# ArduOSD_Simple2222.net
KiCad netlist of a schematic drawn in EAGLE
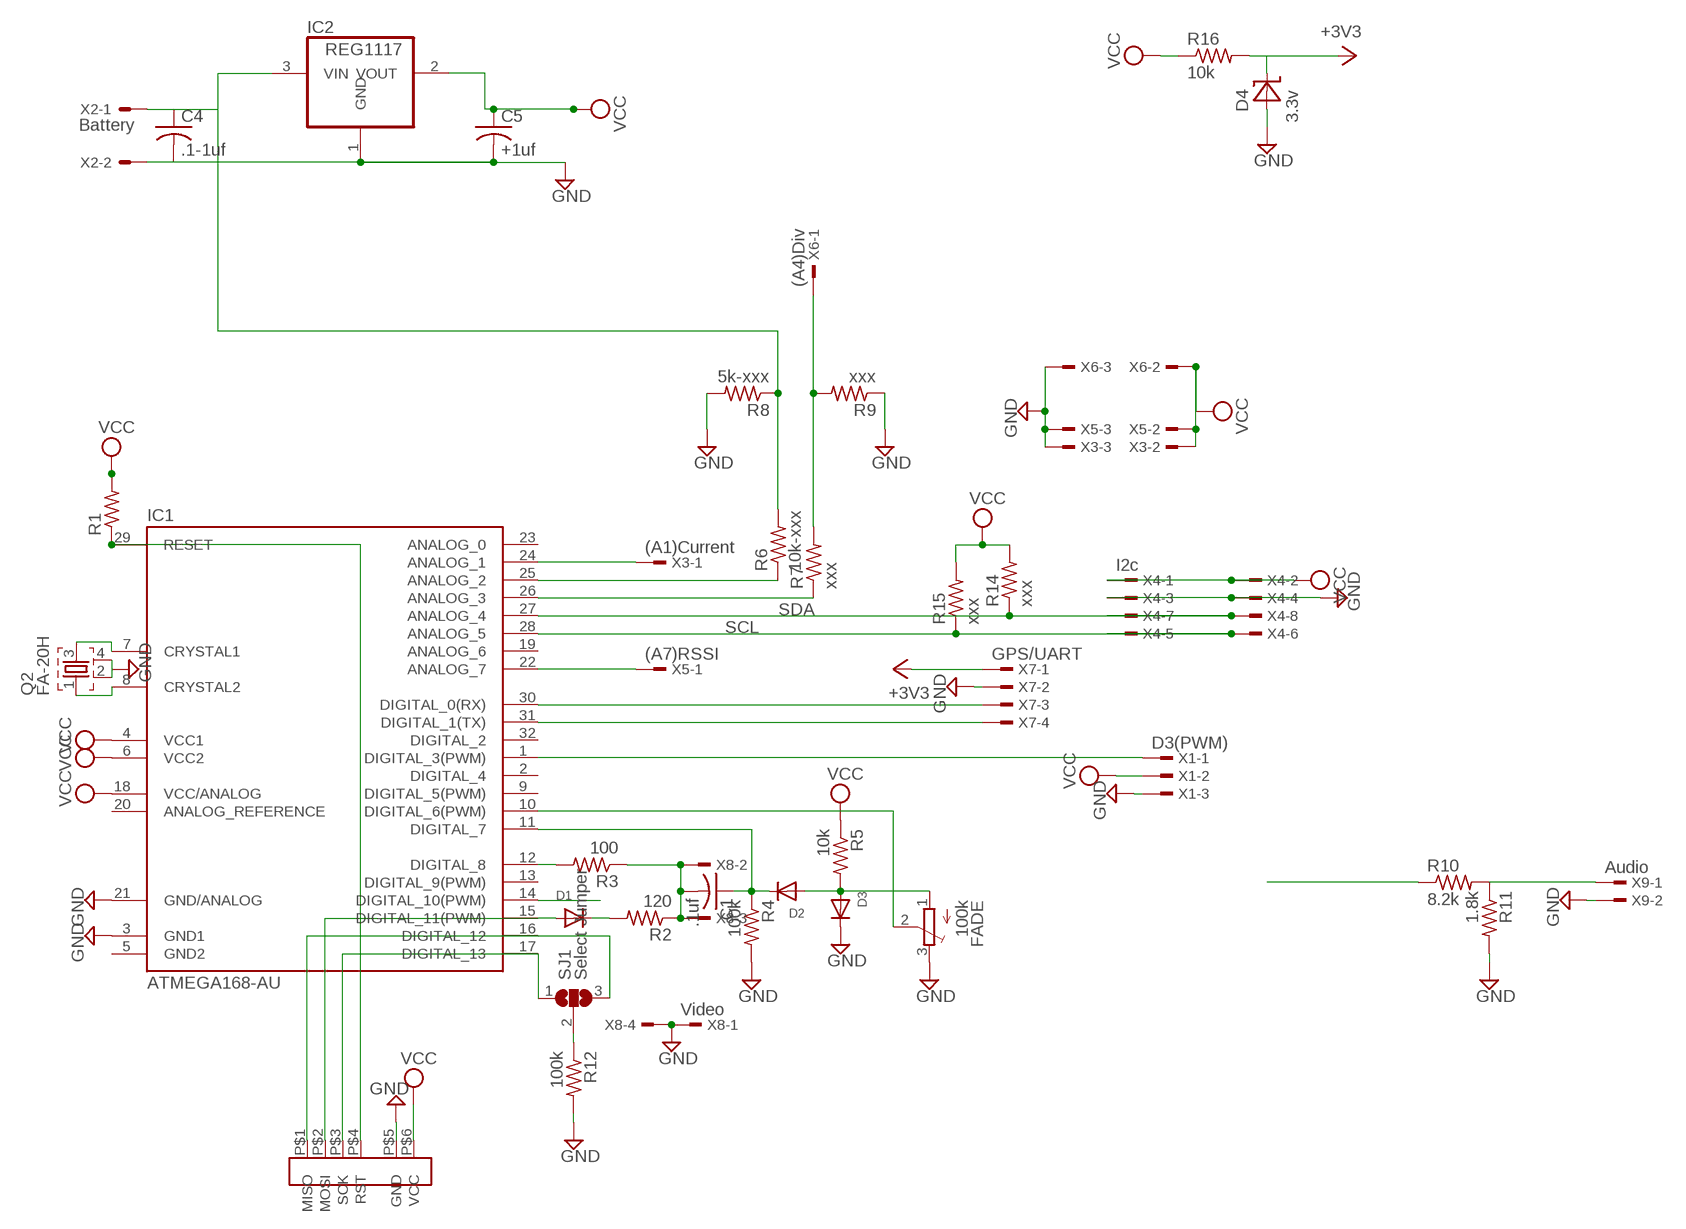
[diagram p0: schematic, sheet 1]

(export (version "E")
  (design (tool "Eeschema 10.0.6"))
  (components
    (comp (ref "C1")
      (value ".1uf")
      (footprint "eagle-import:C0805K")
      (libsource (lib "eagle-import") (part "C-USC0805K"))
    )
    (comp (ref "C4")
      (value ".1-1uf")
      (footprint "eagle-import:C0805K")
      (libsource (lib "eagle-import") (part "C-USC0805K"))
    )
    (comp (ref "C5")
      (value "+1uf")
      (footprint "eagle-import:C0805K")
      (libsource (lib "eagle-import") (part "C-USC0805K"))
    )
    (comp (ref "D1")
      (value "DIODESOT23_WAVE")
      (footprint "eagle-import:SOT23-W")
      (libsource (lib "eagle-import") (part "DIODESOT23_WAVE"))
    )
    (comp (ref "D2")
      (value "DIODESOT23_WAVE")
      (footprint "eagle-import:SOT23-W")
      (libsource (lib "eagle-import") (part "DIODESOT23_WAVE"))
    )
    (comp (ref "D3")
      (value "DIODESOT23_WAVE")
      (footprint "eagle-import:SOT23-W")
      (libsource (lib "eagle-import") (part "DIODESOT23_WAVE"))
    )
    (comp (ref "D4")
      (value "3.3v")
      (footprint "eagle-import:SOD-123")
      (libsource (lib "eagle-import") (part "ZENER_SOD123"))
    )
    (comp (ref "FADE")
      (value "100k")
      (footprint "eagle-import:TC33X")
      (libsource (lib "eagle-import") (part "TRIMPOTTC33X"))
    )
    (comp (ref "IC1")
      (value "ATMEGA168-AU")
      (footprint "eagle-import:TQFP32-08")
      (libsource (lib "eagle-import") (part "ATMEGA168-AU"))
    )
    (comp (ref "IC2")
      (value "REG1117")
      (footprint "eagle-import:SOT223")
      (libsource (lib "eagle-import") (part "REG1117"))
    )
    (comp (ref "Q2")
      (value "FA-20H")
      (footprint "eagle-import:FA-20H")
      (libsource (lib "eagle-import") (part "FA-20H"))
    )
    (comp (ref "R1")
      (value "R-US_R0805")
      (footprint "eagle-import:R0805")
      (libsource (lib "eagle-import") (part "R-US_R0805"))
    )
    (comp (ref "R2")
      (value "120")
      (footprint "eagle-import:R0805")
      (libsource (lib "eagle-import") (part "R-US_R0805"))
    )
    (comp (ref "R3")
      (value "100")
      (footprint "eagle-import:R0805")
      (libsource (lib "eagle-import") (part "R-US_R0805"))
    )
    (comp (ref "R4")
      (value "100k")
      (footprint "eagle-import:R0805")
      (libsource (lib "eagle-import") (part "R-US_R0805"))
    )
    (comp (ref "R5")
      (value "10k")
      (footprint "eagle-import:R0805")
      (libsource (lib "eagle-import") (part "R-US_R0805"))
    )
    (comp (ref "R6")
      (value "10k-xxx")
      (footprint "eagle-import:R0805")
      (libsource (lib "eagle-import") (part "R-US_R0805"))
    )
    (comp (ref "R7")
      (value "xxx")
      (footprint "eagle-import:R0805")
      (libsource (lib "eagle-import") (part "R-US_R0805"))
    )
    (comp (ref "R8")
      (value "5k-xxx")
      (footprint "eagle-import:R0805")
      (libsource (lib "eagle-import") (part "R-US_R0805"))
    )
    (comp (ref "R9")
      (value "xxx")
      (footprint "eagle-import:R0805")
      (libsource (lib "eagle-import") (part "R-US_R0805"))
    )
    (comp (ref "R10")
      (value "8.2k")
      (footprint "eagle-import:R0805")
      (libsource (lib "eagle-import") (part "R-US_R0805"))
    )
    (comp (ref "R11")
      (value "1.8k")
      (footprint "eagle-import:R0805")
      (libsource (lib "eagle-import") (part "R-US_R0805"))
    )
    (comp (ref "R12")
      (value "100k")
      (footprint "eagle-import:R0805")
      (libsource (lib "eagle-import") (part "R-US_R0805"))
    )
    (comp (ref "R14")
      (value "xxx")
      (footprint "eagle-import:R0805")
      (libsource (lib "eagle-import") (part "R-US_R0805"))
    )
    (comp (ref "R15")
      (value "xxx")
      (footprint "eagle-import:R0805")
      (libsource (lib "eagle-import") (part "R-US_R0805"))
    )
    (comp (ref "R16")
      (value "10k")
      (footprint "eagle-import:R0805")
      (libsource (lib "eagle-import") (part "R-US_R0805"))
    )
    (comp (ref "SJ1")
      (value "Select Jumper")
      (footprint "eagle-import:SJ_2")
      (libsource (lib "eagle-import") (part "SJ2W"))
    )
    (comp (ref "U$1")
      (value "LIN_ISP")
      (footprint "eagle-import:LINEAR_ISP")
      (libsource (lib "eagle-import") (part "LIN_ISP"))
    )
    (comp (ref "X1")
      (value "D3(PWM)")
      (footprint "eagle-import:TSW-103-02-S-S")
      (fields (field (name "OC_FARNELL") "unknown") (field (name "OC_NEWARK") "unknown"))
      (libsource (lib "eagle-import") (part "TSW-103-02-S-S"))
    )
    (comp (ref "X2")
      (value "Battery")
      (footprint "eagle-import:22-23-2021")
      (fields (field (name "MF") "MOLEX") (field (name "MPN") "22-23-2021"))
      (libsource (lib "eagle-import") (part "22-23-2021"))
    )
    (comp (ref "X3")
      (value "(A1)Current")
      (footprint "eagle-import:TSW-103-02-S-S")
      (libsource (lib "eagle-import") (part "TSW-103-02-S-S"))
    )
    (comp (ref "X4")
      (value "I2c")
      (footprint "eagle-import:TSW-104-02-S-D-RA")
      (libsource (lib "eagle-import") (part "TSW-104-02-S-D-RA"))
    )
    (comp (ref "X5")
      (value "(A7)RSSI")
      (footprint "eagle-import:TSW-103-02-S-S")
      (libsource (lib "eagle-import") (part "TSW-103-02-S-S"))
    )
    (comp (ref "X6")
      (value "(A4)Div")
      (footprint "eagle-import:TSW-103-02-S-S")
      (fields (field (name "OC_FARNELL") "unknown") (field (name "OC_NEWARK") "unknown"))
      (libsource (lib "eagle-import") (part "TSW-103-02-S-S"))
    )
    (comp (ref "X7")
      (value "GPS/UART")
      (footprint "eagle-import:TSW-104-02-S-S-RA")
      (libsource (lib "eagle-import") (part "TSW-104-02-S-S-RA"))
    )
    (comp (ref "X8")
      (value "Video")
      (footprint "eagle-import:TSW-104-02-S-S-RA")
      (libsource (lib "eagle-import") (part "TSW-104-02-S-S-RA"))
    )
    (comp (ref "X9")
      (value "Audio")
      (footprint "eagle-import:TSW-102-02-S-S-RA")
      (fields (field (name "OC_FARNELL") "unknown") (field (name "OC_NEWARK") "unknown"))
      (libsource (lib "eagle-import") (part "TSW-102-02-S-S-RA"))
    )
  )
  (nets
    (net (code "1") (name "+3V3") (class "Default")
      (node (ref "D4") (pin "1") (pinfunction "C_1") (pintype "passive"))
      (node (ref "R16") (pin "2") (pinfunction "2_2") (pintype "passive"))
      (node (ref "X7") (pin "1") (pinfunction "1_1") (pintype "passive"))
    )
    (net (code "2") (name "/DIGITAL_10") (class "Default")
      (node (ref "IC1") (pin "14") (pinfunction "DIGITAL_10(PWM)_14") (pintype "bidirectional"))
      (node (ref "R10") (pin "1") (pinfunction "1_1") (pintype "passive"))
    )
    (net (code "3") (name "/GND2") (class "Default")
      (node (ref "IC1") (pin "5") (pinfunction "GND2_5") (pintype "power_in"))
    )
    (net (code "4") (name "/SCL") (class "Default")
      (node (ref "IC1") (pin "28") (pinfunction "ANALOG_5_28") (pintype "bidirectional"))
      (node (ref "R15") (pin "1") (pinfunction "1_1") (pintype "passive"))
      (node (ref "X4") (pin "5") (pinfunction "1_5") (pintype "passive"))
      (node (ref "X4") (pin "6") (pinfunction "1_6") (pintype "passive"))
    )
    (net (code "5") (name "/SDA") (class "Default")
      (node (ref "IC1") (pin "27") (pinfunction "ANALOG_4_27") (pintype "bidirectional"))
      (node (ref "R14") (pin "1") (pinfunction "1_1") (pintype "passive"))
      (node (ref "X4") (pin "7") (pinfunction "1_7") (pintype "passive"))
      (node (ref "X4") (pin "8") (pinfunction "1_8") (pintype "passive"))
    )
    (net (code "6") (name "GND") (class "Default")
      (node (ref "C4") (pin "2") (pinfunction "2_2") (pintype "passive"))
      (node (ref "C5") (pin "2") (pinfunction "2_2") (pintype "passive"))
      (node (ref "D3") (pin "3") (pinfunction "C_3") (pintype "passive"))
      (node (ref "D4") (pin "2") (pinfunction "A_2") (pintype "passive"))
      (node (ref "FADE") (pin "3") (pinfunction "E_3") (pintype "passive"))
      (node (ref "IC1") (pin "21") (pinfunction "GND/ANALOG_21") (pintype "power_in"))
      (node (ref "IC1") (pin "3") (pinfunction "GND1_3") (pintype "power_in"))
      (node (ref "IC2") (pin "1") (pinfunction "GND_1") (pintype "power_in"))
      (node (ref "Q2") (pin "2") (pinfunction "2_2") (pintype "passive"))
      (node (ref "Q2") (pin "4") (pinfunction "4_4") (pintype "passive"))
      (node (ref "R11") (pin "2") (pinfunction "2_2") (pintype "passive"))
      (node (ref "R12") (pin "2") (pinfunction "2_2") (pintype "passive"))
      (node (ref "R4") (pin "2") (pinfunction "2_2") (pintype "passive"))
      (node (ref "R8") (pin "2") (pinfunction "2_2") (pintype "passive"))
      (node (ref "R9") (pin "1") (pinfunction "1_1") (pintype "passive"))
      (node (ref "U$1") (pin "P$5") (pinfunction "GND_P$5") (pintype "bidirectional"))
      (node (ref "X1") (pin "3") (pinfunction "1_3") (pintype "passive"))
      (node (ref "X2") (pin "2") (pinfunction "S_2") (pintype "passive"))
      (node (ref "X3") (pin "3") (pinfunction "1_3") (pintype "passive"))
      (node (ref "X4") (pin "3") (pinfunction "1_3") (pintype "passive"))
      (node (ref "X4") (pin "4") (pinfunction "1_4") (pintype "passive"))
      (node (ref "X5") (pin "3") (pinfunction "1_3") (pintype "passive"))
      (node (ref "X6") (pin "3") (pinfunction "1_3") (pintype "passive"))
      (node (ref "X7") (pin "2") (pinfunction "1_2") (pintype "passive"))
      (node (ref "X8") (pin "1") (pinfunction "1_1") (pintype "passive"))
      (node (ref "X8") (pin "4") (pinfunction "1_4") (pintype "passive"))
      (node (ref "X9") (pin "2") (pinfunction "1_2") (pintype "passive"))
    )
    (net (code "7") (name "Net-(D1-A)") (class "Default")
      (node (ref "D1") (pin "1") (pinfunction "A_1") (pintype "passive"))
      (node (ref "IC1") (pin "15") (pinfunction "DIGITAL_11(PWM)_15") (pintype "bidirectional"))
      (node (ref "U$1") (pin "P$2") (pinfunction "MOSI_P$2") (pintype "bidirectional"))
    )
    (net (code "8") (name "Net-(D1-C)") (class "Default")
      (node (ref "D1") (pin "3") (pinfunction "C_3") (pintype "passive"))
      (node (ref "R2") (pin "2") (pinfunction "2_2") (pintype "passive"))
    )
    (net (code "9") (name "Net-(D2-A)") (class "Default")
      (node (ref "D2") (pin "1") (pinfunction "A_1") (pintype "passive"))
      (node (ref "D3") (pin "1") (pinfunction "A_1") (pintype "passive"))
      (node (ref "FADE") (pin "1") (pinfunction "A_1") (pintype "passive"))
      (node (ref "R5") (pin "2") (pinfunction "2_2") (pintype "passive"))
    )
    (net (code "10") (name "Net-(D2-C)") (class "Default")
      (node (ref "C1") (pin "1") (pinfunction "1_1") (pintype "passive"))
      (node (ref "D2") (pin "3") (pinfunction "C_3") (pintype "passive"))
      (node (ref "IC1") (pin "11") (pinfunction "DIGITAL_7_11") (pintype "bidirectional"))
      (node (ref "R4") (pin "1") (pinfunction "1_1") (pintype "passive"))
    )
    (net (code "11") (name "Net-(FADE-S)") (class "Default")
      (node (ref "FADE") (pin "2") (pinfunction "S_2") (pintype "passive"))
      (node (ref "IC1") (pin "10") (pinfunction "DIGITAL_6(PWM)_10") (pintype "bidirectional"))
    )
    (net (code "12") (name "Net-(IC1-ANALOG_1)") (class "Default")
      (node (ref "IC1") (pin "24") (pinfunction "ANALOG_1_24") (pintype "bidirectional"))
      (node (ref "X3") (pin "1") (pinfunction "1_1") (pintype "passive"))
    )
    (net (code "13") (name "Net-(IC1-ANALOG_2)") (class "Default")
      (node (ref "IC1") (pin "25") (pinfunction "ANALOG_2_25") (pintype "bidirectional"))
      (node (ref "R6") (pin "1") (pinfunction "1_1") (pintype "passive"))
    )
    (net (code "14") (name "Net-(IC1-ANALOG_3)") (class "Default")
      (node (ref "IC1") (pin "26") (pinfunction "ANALOG_3_26") (pintype "bidirectional"))
      (node (ref "R7") (pin "1") (pinfunction "1_1") (pintype "passive"))
    )
    (net (code "15") (name "Net-(IC1-ANALOG_7)") (class "Default")
      (node (ref "IC1") (pin "22") (pinfunction "ANALOG_7_22") (pintype "passive"))
      (node (ref "X5") (pin "1") (pinfunction "1_1") (pintype "passive"))
    )
    (net (code "16") (name "Net-(IC1-CRYSTAL1)") (class "Default")
      (node (ref "IC1") (pin "7") (pinfunction "CRYSTAL1_7") (pintype "bidirectional"))
      (node (ref "Q2") (pin "3") (pinfunction "3_3") (pintype "passive"))
    )
    (net (code "17") (name "Net-(IC1-CRYSTAL2)") (class "Default")
      (node (ref "IC1") (pin "8") (pinfunction "CRYSTAL2_8") (pintype "bidirectional"))
      (node (ref "Q2") (pin "1") (pinfunction "1_1") (pintype "passive"))
    )
    (net (code "18") (name "Net-(IC1-DIGITAL_0(RX))") (class "Default")
      (node (ref "IC1") (pin "30") (pinfunction "DIGITAL_0(RX)_30") (pintype "bidirectional"))
      (node (ref "X7") (pin "3") (pinfunction "1_3") (pintype "passive"))
    )
    (net (code "19") (name "Net-(IC1-DIGITAL_1(TX))") (class "Default")
      (node (ref "IC1") (pin "31") (pinfunction "DIGITAL_1(TX)_31") (pintype "bidirectional"))
      (node (ref "X7") (pin "4") (pinfunction "1_4") (pintype "passive"))
    )
    (net (code "20") (name "Net-(IC1-DIGITAL_3(PWM))") (class "Default")
      (node (ref "IC1") (pin "1") (pinfunction "DIGITAL_3(PWM)_1") (pintype "bidirectional"))
      (node (ref "X1") (pin "1") (pinfunction "1_1") (pintype "passive"))
    )
    (net (code "21") (name "Net-(IC1-DIGITAL_8)") (class "Default")
      (node (ref "IC1") (pin "12") (pinfunction "DIGITAL_8_12") (pintype "bidirectional"))
      (node (ref "R3") (pin "2") (pinfunction "2_2") (pintype "passive"))
    )
    (net (code "22") (name "Net-(IC1-DIGITAL_12)") (class "Default")
      (node (ref "IC1") (pin "16") (pinfunction "DIGITAL_12_16") (pintype "bidirectional"))
      (node (ref "SJ1") (pin "3") (pinfunction "3_3") (pintype "passive"))
      (node (ref "U$1") (pin "P$1") (pinfunction "MISO_P$1") (pintype "bidirectional"))
    )
    (net (code "23") (name "Net-(IC1-DIGITAL_13)") (class "Default")
      (node (ref "IC1") (pin "17") (pinfunction "DIGITAL_13_17") (pintype "bidirectional"))
      (node (ref "SJ1") (pin "1") (pinfunction "1_1") (pintype "passive"))
      (node (ref "U$1") (pin "P$3") (pinfunction "SCK_P$3") (pintype "bidirectional"))
    )
    (net (code "24") (name "Net-(IC1-RESET)") (class "Default")
      (node (ref "IC1") (pin "29") (pinfunction "RESET_29") (pintype "bidirectional"))
      (node (ref "R1") (pin "1") (pinfunction "1_1") (pintype "passive"))
      (node (ref "U$1") (pin "P$4") (pinfunction "RST_P$4") (pintype "bidirectional"))
    )
    (net (code "25") (name "Net-(IC2-VIN)") (class "Default")
      (node (ref "C4") (pin "1") (pinfunction "1_1") (pintype "passive"))
      (node (ref "IC2") (pin "3") (pinfunction "VIN_3") (pintype "input"))
      (node (ref "R6") (pin "2") (pinfunction "2_2") (pintype "passive"))
      (node (ref "R8") (pin "1") (pinfunction "1_1") (pintype "passive"))
      (node (ref "X2") (pin "1") (pinfunction "S_1") (pintype "passive"))
    )
    (net (code "26") (name "Net-(R7-Pad2)") (class "Default")
      (node (ref "R7") (pin "2") (pinfunction "2_2") (pintype "passive"))
      (node (ref "R9") (pin "2") (pinfunction "2_2") (pintype "passive"))
      (node (ref "X6") (pin "1") (pinfunction "1_1") (pintype "passive"))
    )
    (net (code "27") (name "Net-(R10-Pad2)") (class "Default")
      (node (ref "R10") (pin "2") (pinfunction "2_2") (pintype "passive"))
      (node (ref "R11") (pin "1") (pinfunction "1_1") (pintype "passive"))
      (node (ref "X9") (pin "1") (pinfunction "1_1") (pintype "passive"))
    )
    (net (code "28") (name "Net-(R12-Pad1)") (class "Default")
      (node (ref "R12") (pin "1") (pinfunction "1_1") (pintype "passive"))
      (node (ref "SJ1") (pin "2") (pinfunction "2_2") (pintype "passive"))
    )
    (net (code "29") (name "Net-(X8B-1)") (class "Default")
      (node (ref "C1") (pin "2") (pinfunction "2_2") (pintype "passive"))
      (node (ref "R2") (pin "1") (pinfunction "1_1") (pintype "passive"))
      (node (ref "R3") (pin "1") (pinfunction "1_1") (pintype "passive"))
      (node (ref "X8") (pin "2") (pinfunction "1_2") (pintype "passive"))
      (node (ref "X8") (pin "3") (pinfunction "1_3") (pintype "passive"))
    )
    (net (code "30") (name "VCC") (class "Default")
      (node (ref "C5") (pin "1") (pinfunction "1_1") (pintype "passive"))
      (node (ref "IC1") (pin "18") (pinfunction "VCC/ANALOG_18") (pintype "passive"))
      (node (ref "IC1") (pin "4") (pinfunction "VCC1_4") (pintype "power_in"))
      (node (ref "IC1") (pin "6") (pinfunction "VCC2_6") (pintype "power_in"))
      (node (ref "IC2") (pin "2") (pinfunction "VOUT_2") (pintype "output"))
      (node (ref "R1") (pin "2") (pinfunction "2_2") (pintype "passive"))
      (node (ref "R14") (pin "2") (pinfunction "2_2") (pintype "passive"))
      (node (ref "R15") (pin "2") (pinfunction "2_2") (pintype "passive"))
      (node (ref "R16") (pin "1") (pinfunction "1_1") (pintype "passive"))
      (node (ref "R5") (pin "1") (pinfunction "1_1") (pintype "passive"))
      (node (ref "U$1") (pin "P$6") (pinfunction "VCC_P$6") (pintype "bidirectional"))
      (node (ref "X1") (pin "2") (pinfunction "1_2") (pintype "passive"))
      (node (ref "X3") (pin "2") (pinfunction "1_2") (pintype "passive"))
      (node (ref "X4") (pin "1") (pinfunction "1_1") (pintype "passive"))
      (node (ref "X4") (pin "2") (pinfunction "1_2") (pintype "passive"))
      (node (ref "X5") (pin "2") (pinfunction "1_2") (pintype "passive"))
      (node (ref "X6") (pin "2") (pinfunction "1_2") (pintype "passive"))
    )
    (net (code "31") (name "unconnected-(IC1-ANALOG_0-Pad23)") (class "Default")
      (node (ref "IC1") (pin "23") (pinfunction "ANALOG_0_23") (pintype "bidirectional"))
    )
    (net (code "32") (name "unconnected-(IC1-ANALOG_6-Pad19)") (class "Default")
      (node (ref "IC1") (pin "19") (pinfunction "ANALOG_6_19") (pintype "passive"))
    )
    (net (code "33") (name "unconnected-(IC1-ANALOG_REFERENCE-Pad20)") (class "Default")
      (node (ref "IC1") (pin "20") (pinfunction "ANALOG_REFERENCE_20") (pintype "passive"))
    )
    (net (code "34") (name "unconnected-(IC1-DIGITAL_2-Pad32)") (class "Default")
      (node (ref "IC1") (pin "32") (pinfunction "DIGITAL_2_32") (pintype "bidirectional"))
    )
    (net (code "35") (name "unconnected-(IC1-DIGITAL_4-Pad2)") (class "Default")
      (node (ref "IC1") (pin "2") (pinfunction "DIGITAL_4_2") (pintype "bidirectional"))
    )
    (net (code "36") (name "unconnected-(IC1-DIGITAL_5(PWM)-Pad9)") (class "Default")
      (node (ref "IC1") (pin "9") (pinfunction "DIGITAL_5(PWM)_9") (pintype "bidirectional"))
    )
    (net (code "37") (name "unconnected-(IC1-DIGITAL_9(PWM)-Pad13)") (class "Default")
      (node (ref "IC1") (pin "13") (pinfunction "DIGITAL_9(PWM)_13") (pintype "bidirectional"))
    )
  )
)
